# 08-multimodal-microcontroller-oscillator.net
KiCad netlist of a schematic drawn in Altium Designer
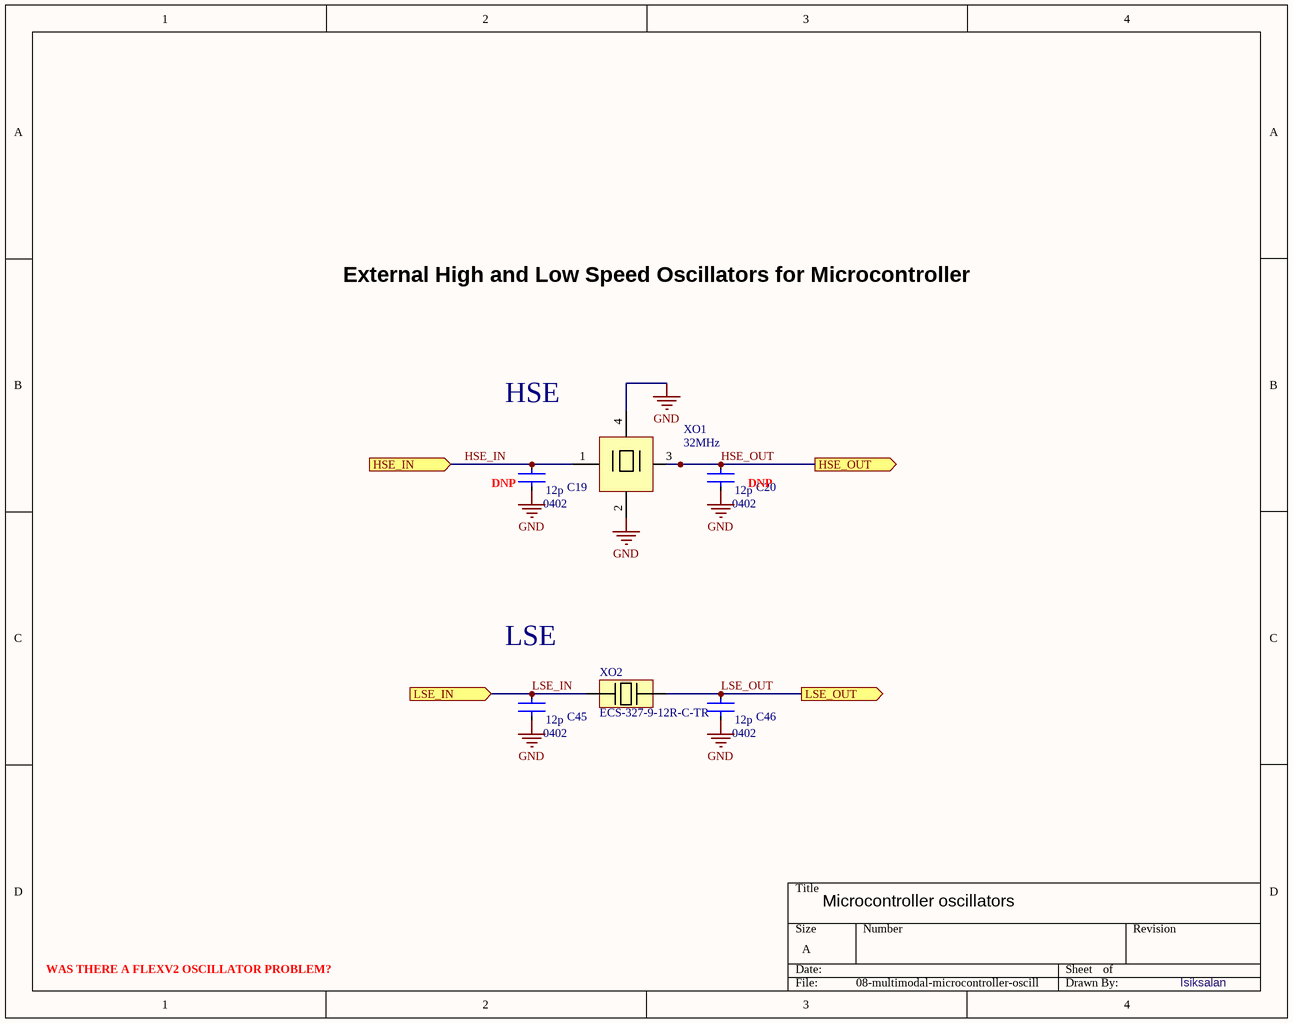
[diagram p0: 08-multimodal-microcontroller-oscillators.SchDoc]

(export (version "E")
  (design (tool "Eeschema 10.0.6"))
  (components
    (comp (ref "C19")
      (value "CGA2B2C0G1H120J050BA")
      (footprint "CAPTDK0402")
      (description "CAP CER 12PF 50V C0G 0402")
      (libsource (lib "multimodal") (part "CGA2B2C0G1H120J050BA"))
    )
    (comp (ref "C20")
      (value "CGA2B2C0G1H120J050BA")
      (footprint "CAPTDK0402")
      (description "CAP CER 12PF 50V C0G 0402")
      (libsource (lib "multimodal") (part "CGA2B2C0G1H120J050BA"))
    )
    (comp (ref "C45")
      (value "CGA2B2C0G1H120J050BA")
      (footprint "CAPTDK0402")
      (description "CAP CER 12PF 50V C0G 0402")
      (libsource (lib "multimodal") (part "CGA2B2C0G1H120J050BA"))
    )
    (comp (ref "C46")
      (value "CGA2B2C0G1H120J050BA")
      (footprint "CAPTDK0402")
      (description "CAP CER 12PF 50V C0G 0402")
      (libsource (lib "multimodal") (part "CGA2B2C0G1H120J050BA"))
    )
    (comp (ref "XO1")
      (value "32MHz")
      (footprint "HSE-32MHZ")
      (description "CRYSTAL 32MHZ 8PF 60R SMD")
      (fields
        (field (name "MANUFACTURER") "NDK")
        (field (name "MANUFACTURER PART NUMBER") "NX2016SA-32MHZ-EXS00A-CS06654")
      )
      (libsource (lib "multimodal") (part "NX2016SA-32MHZ-EXS00A-CS06654"))
    )
    (comp (ref "XO2")
      (value "ECS-327-9-12R-C-TR")
      (footprint "LSE-32K")
      (description "Crystal 0.032768MHz ±10ppm (Tol) 9pF Flexural 70000Ohm Automotive 2-Pin Ultra Mini-CSMD T/R")
      (fields
        (field (name "MANUFACTURER") "ECS International")
        (field (name "MANUFACTURER PART NUMBER") "ECS-.327-9-12R-C-TR")
      )
      (libsource (lib "multimodal") (part "ECS-327-9-12R-C-TR"))
    )
  )
  (nets
    (net (code "1") (name "/HSE_IN") (class "Default")
      (node (ref "C19") (pin "1") (pinfunction "1_1") (pintype "passive"))
      (node (ref "XO1") (pin "1") (pinfunction "1_1") (pintype "passive"))
    )
    (net (code "2") (name "/HSE_OUT") (class "Default")
      (node (ref "C20") (pin "1") (pinfunction "1_1") (pintype "passive"))
      (node (ref "XO1") (pin "3") (pinfunction "3_3") (pintype "passive"))
    )
    (net (code "3") (name "/LSE_IN") (class "Default")
      (node (ref "C45") (pin "1") (pinfunction "1_1") (pintype "passive"))
      (node (ref "XO2") (pin "1") (pinfunction "1_1") (pintype "passive"))
    )
    (net (code "4") (name "/LSE_OUT") (class "Default")
      (node (ref "C46") (pin "1") (pinfunction "1_1") (pintype "passive"))
      (node (ref "XO2") (pin "2") (pinfunction "2_2") (pintype "passive"))
    )
    (net (code "5") (name "GND") (class "Default")
      (node (ref "C19") (pin "2") (pinfunction "2_2") (pintype "passive"))
      (node (ref "C20") (pin "2") (pinfunction "2_2") (pintype "passive"))
      (node (ref "C45") (pin "2") (pinfunction "2_2") (pintype "passive"))
      (node (ref "C46") (pin "2") (pinfunction "2_2") (pintype "passive"))
      (node (ref "XO1") (pin "2") (pinfunction "2_2") (pintype "passive"))
      (node (ref "XO1") (pin "4") (pinfunction "4_4") (pintype "passive"))
    )
  )
)
